# 4_ADC.net
KiCad netlist of a schematic drawn in Altium Designer
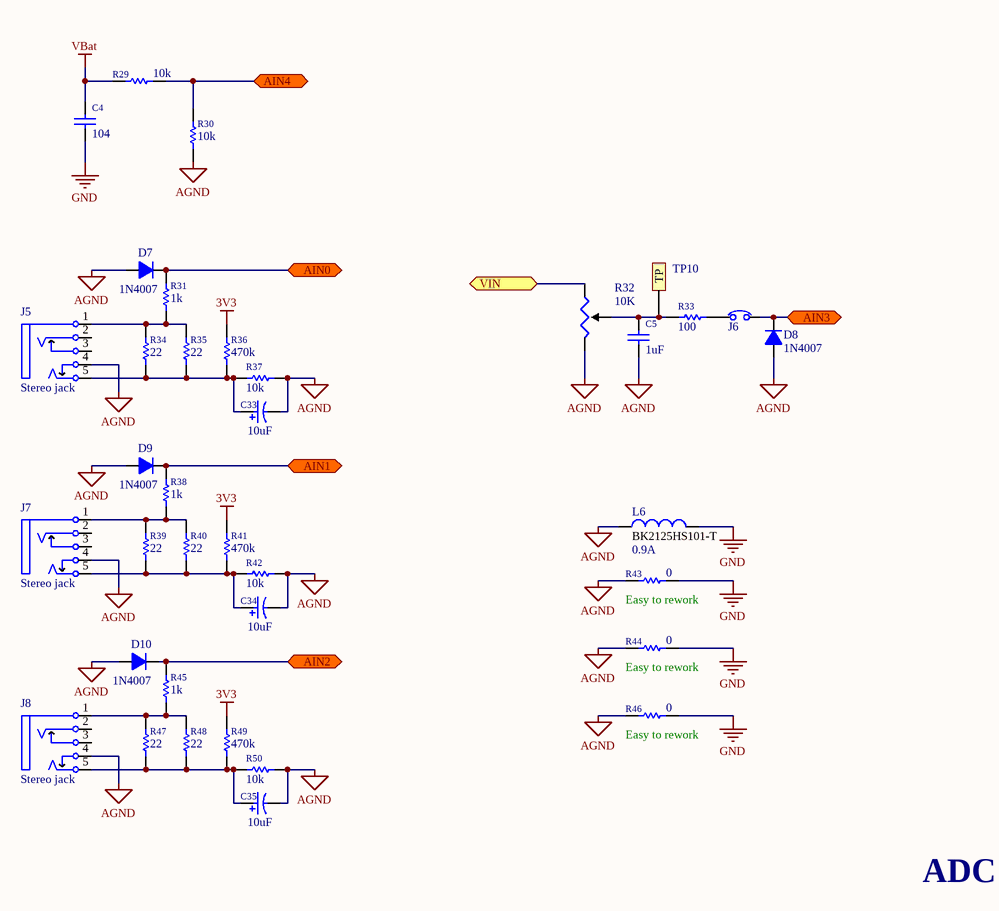
[diagram p0: 4. ADC.SchDoc]

(export (version "E")
  (design (tool "Eeschema 10.0.6"))
  (components
    (comp (ref "C4")
      (value "104")
      (footprint "sm-0603-c")
      (description "CAP CER 10000PF 16V 0603")
      (fields (field (name "MANUFACTURER") "Taiyo Yuden") (field (name "PART") "EMK107SD103JA-T"))
      (libsource (lib "My_Integrated_Library") (part "Capacitor"))
    )
    (comp (ref "C5")
      (value "1uF")
      (footprint "sm-0603-c")
      (description "CAP CER 10000PF 16V 0603")
      (fields (field (name "MANUFACTURER") "Taiyo Yuden") (field (name "PART") "EMK107SD103JA-T"))
      (libsource (lib "My_Integrated_Library") (part "Capacitor"))
    )
    (comp (ref "C33")
      (value "10uF")
      (footprint "Cap SMD Tant 10u")
      (description "CAP CER 10UF 6.3V X5R 1206")
      (fields (field (name "MANUFACTURER") "Samsung Electro-Mechanics") (field (name "VOLTAGE") "6.3V"))
      (libsource (lib "My_Integrated_Library") (part "Cap_Pol"))
    )
    (comp (ref "C34")
      (value "10uF")
      (footprint "Cap SMD Tant 10u")
      (description "CAP CER 10UF 6.3V X5R 1206")
      (fields (field (name "MANUFACTURER") "Samsung Electro-Mechanics") (field (name "VOLTAGE") "6.3V"))
      (libsource (lib "My_Integrated_Library") (part "Cap_Pol"))
    )
    (comp (ref "C35")
      (value "10uF")
      (footprint "Cap SMD Tant 10u")
      (description "CAP CER 10UF 6.3V X5R 1206")
      (fields (field (name "MANUFACTURER") "Samsung Electro-Mechanics") (field (name "VOLTAGE") "6.3V"))
      (libsource (lib "My_Integrated_Library") (part "Cap_Pol"))
    )
    (comp (ref "D7")
      (value "1N4007")
      (footprint "SOD-123")
      (description "DIODE 100V/1A")
      (fields (field (name "PART") "Diode 1N4007") (field (name "MANUFACTURER") "TOSHIBA"))
      (libsource (lib "My_Integrated_Library") (part "Diode 1N4007"))
    )
    (comp (ref "D8")
      (value "1N4007")
      (footprint "SOD-123")
      (description "DIODE 100V/1A")
      (fields (field (name "PART") "Diode 1N4007") (field (name "MANUFACTURER") "TOSHIBA"))
      (libsource (lib "My_Integrated_Library") (part "Diode 1N4007"))
    )
    (comp (ref "D9")
      (value "1N4007")
      (footprint "SOD-123")
      (description "DIODE 100V/1A")
      (fields (field (name "PART") "Diode 1N4007") (field (name "MANUFACTURER") "TOSHIBA"))
      (libsource (lib "My_Integrated_Library") (part "Diode 1N4007"))
    )
    (comp (ref "D10")
      (value "1N4007")
      (footprint "SOD-123")
      (description "DIODE 100V/1A")
      (fields (field (name "PART") "Diode 1N4007") (field (name "MANUFACTURER") "TOSHIBA"))
      (libsource (lib "My_Integrated_Library") (part "Diode 1N4007"))
    )
    (comp (ref "J5")
      (value "Stereo jack")
      (footprint "Audio Stereo Jack")
      (description "Stereo audio jack")
      (libsource (lib "SangNgocLe") (part "Audio Jack"))
    )
    (comp (ref "J6")
      (value "jumper selector")
      (footprint "CON.HDR1X2")
      (libsource (lib "My_Integrated_Library") (part "jumper selector"))
    )
    (comp (ref "J7")
      (value "Stereo jack")
      (footprint "Audio Stereo Jack")
      (description "Stereo audio jack")
      (libsource (lib "SangNgocLe") (part "Audio Jack"))
    )
    (comp (ref "J8")
      (value "Stereo jack")
      (footprint "Audio Stereo Jack")
      (description "Stereo audio jack")
      (libsource (lib "SangNgocLe") (part "Audio Jack"))
    )
    (comp (ref "L6")
      (value "BK2125HS101-T")
      (footprint "L2012-0805")
      (description "FERRITE BEAD 100 OHM 0805 1LN")
      (fields (field (name "MANUFACTURER") "Taiyo Yuden") (field (name "CURRENT") "0.9A"))
      (libsource (lib "My_Integrated_Library") (part "Inductor"))
    )
    (comp (ref "R29")
      (value "10k")
      (footprint "SM-0603-R")
      (description "RES SMD 10K OHM 5% 1/10W 0603")
      (fields (field (name "MANUFACTURER") "Panasonic Electronic Components") (field (name "POWER") "1/10W"))
      (libsource (lib "My_Integrated_Library") (part "Resistor"))
    )
    (comp (ref "R30")
      (value "10k")
      (footprint "SM-0603-R")
      (description "RES SMD 10K OHM 5% 1/10W 0603")
      (fields (field (name "MANUFACTURER") "Panasonic Electronic Components") (field (name "POWER") "1/10W"))
      (libsource (lib "My_Integrated_Library") (part "Resistor"))
    )
    (comp (ref "R31")
      (value "1k")
      (footprint "SM-0603-R")
      (description "RES SMD 10K OHM 5% 1/10W 0603")
      (fields (field (name "MANUFACTURER") "Panasonic Electronic Components") (field (name "PART") "10k"))
      (libsource (lib "My_Integrated_Library") (part "Resistor"))
    )
    (comp (ref "R32")
      (value "10K")
      (footprint "TRIM Rect")
      (description "Res var, Rectangle Trimmer")
      (fields (field (name "PART") "Trimmer"))
      (libsource (lib "My_Integrated_Library") (part "Trimmer"))
    )
    (comp (ref "R33")
      (value "100")
      (footprint "SM-0603-R")
      (description "RES SMD 10K OHM 5% 1/10W 0603")
      (fields (field (name "MANUFACTURER") "Panasonic Electronic Components") (field (name "PART") "10k"))
      (libsource (lib "My_Integrated_Library") (part "Resistor"))
    )
    (comp (ref "R34")
      (value "22")
      (footprint "SM-RES-1206")
      (description "RES SMD 10K OHM 5% 1/10W 0603")
      (fields (field (name "MANUFACTURER") "Panasonic Electronic Components") (field (name "PART") "10k"))
      (libsource (lib "My_Integrated_Library") (part "Resistor"))
    )
    (comp (ref "R35")
      (value "22")
      (footprint "SM-0603-R")
      (description "RES SMD 10K OHM 5% 1/10W 0603")
      (fields (field (name "MANUFACTURER") "Panasonic Electronic Components") (field (name "PART") "10k"))
      (libsource (lib "My_Integrated_Library") (part "Resistor"))
    )
    (comp (ref "R36")
      (value "470k")
      (footprint "SM-0603-R")
      (description "RES SMD 10K OHM 5% 1/10W 0603")
      (fields (field (name "MANUFACTURER") "Panasonic Electronic Components") (field (name "PART") "10k"))
      (libsource (lib "My_Integrated_Library") (part "Resistor"))
    )
    (comp (ref "R37")
      (value "10k")
      (footprint "SM-0603-R")
      (description "RES SMD 10K OHM 5% 1/10W 0603")
      (fields (field (name "MANUFACTURER") "Panasonic Electronic Components") (field (name "POWER") "1/10W"))
      (libsource (lib "My_Integrated_Library") (part "Resistor"))
    )
    (comp (ref "R38")
      (value "1k")
      (footprint "SM-0603-R")
      (description "RES SMD 10K OHM 5% 1/10W 0603")
      (fields (field (name "MANUFACTURER") "Panasonic Electronic Components") (field (name "PART") "10k"))
      (libsource (lib "My_Integrated_Library") (part "Resistor"))
    )
    (comp (ref "R39")
      (value "22")
      (footprint "SM-RES-1206")
      (description "RES SMD 10K OHM 5% 1/10W 0603")
      (fields (field (name "MANUFACTURER") "Panasonic Electronic Components") (field (name "PART") "10k"))
      (libsource (lib "My_Integrated_Library") (part "Resistor"))
    )
    (comp (ref "R40")
      (value "22")
      (footprint "SM-0603-R")
      (description "RES SMD 10K OHM 5% 1/10W 0603")
      (fields (field (name "MANUFACTURER") "Panasonic Electronic Components") (field (name "PART") "10k"))
      (libsource (lib "My_Integrated_Library") (part "Resistor"))
    )
    (comp (ref "R41")
      (value "470k")
      (footprint "SM-0603-R")
      (description "RES SMD 10K OHM 5% 1/10W 0603")
      (fields (field (name "MANUFACTURER") "Panasonic Electronic Components") (field (name "PART") "10k"))
      (libsource (lib "My_Integrated_Library") (part "Resistor"))
    )
    (comp (ref "R42")
      (value "10k")
      (footprint "SM-0603-R")
      (description "RES SMD 10K OHM 5% 1/10W 0603")
      (fields (field (name "MANUFACTURER") "Panasonic Electronic Components") (field (name "POWER") "1/10W"))
      (libsource (lib "My_Integrated_Library") (part "Resistor"))
    )
    (comp (ref "R43")
      (value "0")
      (footprint "R2012-0805")
      (description "RES SMD 0 OHM JUMPER 1/10W 0805")
      (fields (field (name "MANUFACTURER") "Panasonic Electronic Components") (field (name "POWER") "1/10W"))
      (libsource (lib "My_Integrated_Library") (part "Resistor"))
    )
    (comp (ref "R44")
      (value "0")
      (footprint "R2012-0805")
      (description "RES SMD 0 OHM JUMPER 1/10W 0805")
      (fields (field (name "MANUFACTURER") "Panasonic Electronic Components") (field (name "POWER") "1/10W"))
      (libsource (lib "My_Integrated_Library") (part "Resistor"))
    )
    (comp (ref "R45")
      (value "1k")
      (footprint "SM-0603-R")
      (description "RES SMD 10K OHM 5% 1/10W 0603")
      (fields (field (name "MANUFACTURER") "Panasonic Electronic Components") (field (name "PART") "10k"))
      (libsource (lib "My_Integrated_Library") (part "Resistor"))
    )
    (comp (ref "R46")
      (value "0")
      (footprint "R2012-0805")
      (description "RES SMD 0 OHM JUMPER 1/10W 0805")
      (fields (field (name "MANUFACTURER") "Panasonic Electronic Components") (field (name "POWER") "1/10W"))
      (libsource (lib "My_Integrated_Library") (part "Resistor"))
    )
    (comp (ref "R47")
      (value "22")
      (footprint "SM-RES-1206")
      (description "RES SMD 10K OHM 5% 1/10W 0603")
      (fields (field (name "MANUFACTURER") "Panasonic Electronic Components") (field (name "PART") "10k"))
      (libsource (lib "My_Integrated_Library") (part "Resistor"))
    )
    (comp (ref "R48")
      (value "22")
      (footprint "SM-0603-R")
      (description "RES SMD 10K OHM 5% 1/10W 0603")
      (fields (field (name "MANUFACTURER") "Panasonic Electronic Components") (field (name "PART") "10k"))
      (libsource (lib "My_Integrated_Library") (part "Resistor"))
    )
    (comp (ref "R49")
      (value "470k")
      (footprint "SM-0603-R")
      (description "RES SMD 10K OHM 5% 1/10W 0603")
      (fields (field (name "MANUFACTURER") "Panasonic Electronic Components") (field (name "PART") "10k"))
      (libsource (lib "My_Integrated_Library") (part "Resistor"))
    )
    (comp (ref "R50")
      (value "10k")
      (footprint "SM-0603-R")
      (description "RES SMD 10K OHM 5% 1/10W 0603")
      (fields (field (name "MANUFACTURER") "Panasonic Electronic Components") (field (name "POWER") "1/10W"))
      (libsource (lib "My_Integrated_Library") (part "Resistor"))
    )
    (comp (ref "TP10")
      (value "4V3_PG")
      (footprint "TP")
      (description "Test Point")
      (libsource (lib "My_Integrated_Library") (part "Test Point"))
    )
  )
  (nets
    (net (code "1") (name "/AIN0") (class "Default")
      (node (ref "D7") (pin "2") (pinfunction "K_2") (pintype "passive"))
      (node (ref "R31") (pin "2") (pinfunction "2_2") (pintype "passive"))
    )
    (net (code "2") (name "/AIN1") (class "Default")
      (node (ref "D9") (pin "2") (pinfunction "K_2") (pintype "passive"))
      (node (ref "R38") (pin "2") (pinfunction "2_2") (pintype "passive"))
    )
    (net (code "3") (name "/AIN2") (class "Default")
      (node (ref "D10") (pin "2") (pinfunction "K_2") (pintype "passive"))
      (node (ref "R45") (pin "2") (pinfunction "2_2") (pintype "passive"))
    )
    (net (code "4") (name "/AIN3") (class "Default")
      (node (ref "D8") (pin "2") (pinfunction "K_2") (pintype "passive"))
      (node (ref "J6") (pin "2") (pinfunction "2_2") (pintype "passive"))
    )
    (net (code "5") (name "/AIN4") (class "Default")
      (node (ref "R29") (pin "2") (pinfunction "2_2") (pintype "passive"))
      (node (ref "R30") (pin "2") (pinfunction "2_2") (pintype "passive"))
    )
    (net (code "6") (name "/VIN") (class "Default")
      (node (ref "R32") (pin "1") (pinfunction "1_1") (pintype "passive"))
    )
    (net (code "7") (name "3V3") (class "Default")
      (node (ref "R36") (pin "2") (pinfunction "2_2") (pintype "passive"))
      (node (ref "R41") (pin "2") (pinfunction "2_2") (pintype "passive"))
      (node (ref "R49") (pin "2") (pinfunction "2_2") (pintype "passive"))
    )
    (net (code "8") (name "AGND") (class "Default")
      (node (ref "C33") (pin "2") (pinfunction "2_2") (pintype "passive"))
      (node (ref "C34") (pin "2") (pinfunction "2_2") (pintype "passive"))
      (node (ref "C35") (pin "2") (pinfunction "2_2") (pintype "passive"))
      (node (ref "C5") (pin "2") (pinfunction "2_2") (pintype "passive"))
      (node (ref "D10") (pin "1") (pinfunction "A_1") (pintype "passive"))
      (node (ref "D7") (pin "1") (pinfunction "A_1") (pintype "passive"))
      (node (ref "D8") (pin "1") (pinfunction "A_1") (pintype "passive"))
      (node (ref "D9") (pin "1") (pinfunction "A_1") (pintype "passive"))
      (node (ref "J5") (pin "4") (pinfunction "R2_4") (pintype "power_in"))
      (node (ref "J7") (pin "4") (pinfunction "R2_4") (pintype "power_in"))
      (node (ref "J8") (pin "4") (pinfunction "R2_4") (pintype "power_in"))
      (node (ref "L6") (pin "1") (pinfunction "1_1") (pintype "passive"))
      (node (ref "R30") (pin "1") (pinfunction "1_1") (pintype "passive"))
      (node (ref "R32") (pin "3") (pinfunction "3_3") (pintype "passive"))
      (node (ref "R37") (pin "1") (pinfunction "1_1") (pintype "passive"))
      (node (ref "R42") (pin "1") (pinfunction "1_1") (pintype "passive"))
      (node (ref "R43") (pin "1") (pinfunction "1_1") (pintype "passive"))
      (node (ref "R44") (pin "1") (pinfunction "1_1") (pintype "passive"))
      (node (ref "R46") (pin "1") (pinfunction "1_1") (pintype "passive"))
      (node (ref "R50") (pin "1") (pinfunction "1_1") (pintype "passive"))
    )
    (net (code "9") (name "GND") (class "Default")
      (node (ref "C4") (pin "2") (pinfunction "2_2") (pintype "passive"))
      (node (ref "L6") (pin "2") (pinfunction "2_2") (pintype "passive"))
      (node (ref "R43") (pin "2") (pinfunction "2_2") (pintype "passive"))
      (node (ref "R44") (pin "2") (pinfunction "2_2") (pintype "passive"))
      (node (ref "R46") (pin "2") (pinfunction "2_2") (pintype "passive"))
    )
    (net (code "10") (name "Net-(J5-GND)") (class "Default")
      (node (ref "J5") (pin "1") (pinfunction "GND_1") (pintype "passive"))
      (node (ref "R31") (pin "1") (pinfunction "1_1") (pintype "passive"))
      (node (ref "R34") (pin "2") (pinfunction "2_2") (pintype "passive"))
      (node (ref "R35") (pin "2") (pinfunction "2_2") (pintype "passive"))
    )
    (net (code "11") (name "Net-(J5-S2)") (class "Default")
      (node (ref "C33") (pin "1") (pinfunction "1_1") (pintype "passive"))
      (node (ref "J5") (pin "5") (pinfunction "S2_5") (pintype "power_in"))
      (node (ref "R34") (pin "1") (pinfunction "1_1") (pintype "passive"))
      (node (ref "R35") (pin "1") (pinfunction "1_1") (pintype "passive"))
      (node (ref "R36") (pin "1") (pinfunction "1_1") (pintype "passive"))
      (node (ref "R37") (pin "2") (pinfunction "2_2") (pintype "passive"))
    )
    (net (code "12") (name "Net-(J6-Pad1)") (class "Default")
      (node (ref "J6") (pin "1") (pinfunction "1_1") (pintype "passive"))
      (node (ref "R33") (pin "1") (pinfunction "1_1") (pintype "passive"))
    )
    (net (code "13") (name "Net-(J7-GND)") (class "Default")
      (node (ref "J7") (pin "1") (pinfunction "GND_1") (pintype "passive"))
      (node (ref "R38") (pin "1") (pinfunction "1_1") (pintype "passive"))
      (node (ref "R39") (pin "2") (pinfunction "2_2") (pintype "passive"))
      (node (ref "R40") (pin "2") (pinfunction "2_2") (pintype "passive"))
    )
    (net (code "14") (name "Net-(J7-S2)") (class "Default")
      (node (ref "C34") (pin "1") (pinfunction "1_1") (pintype "passive"))
      (node (ref "J7") (pin "5") (pinfunction "S2_5") (pintype "power_in"))
      (node (ref "R39") (pin "1") (pinfunction "1_1") (pintype "passive"))
      (node (ref "R40") (pin "1") (pinfunction "1_1") (pintype "passive"))
      (node (ref "R41") (pin "1") (pinfunction "1_1") (pintype "passive"))
      (node (ref "R42") (pin "2") (pinfunction "2_2") (pintype "passive"))
    )
    (net (code "15") (name "Net-(J8-GND)") (class "Default")
      (node (ref "J8") (pin "1") (pinfunction "GND_1") (pintype "passive"))
      (node (ref "R45") (pin "1") (pinfunction "1_1") (pintype "passive"))
      (node (ref "R47") (pin "2") (pinfunction "2_2") (pintype "passive"))
      (node (ref "R48") (pin "2") (pinfunction "2_2") (pintype "passive"))
    )
    (net (code "16") (name "Net-(J8-S2)") (class "Default")
      (node (ref "C35") (pin "1") (pinfunction "1_1") (pintype "passive"))
      (node (ref "J8") (pin "5") (pinfunction "S2_5") (pintype "power_in"))
      (node (ref "R47") (pin "1") (pinfunction "1_1") (pintype "passive"))
      (node (ref "R48") (pin "1") (pinfunction "1_1") (pintype "passive"))
      (node (ref "R49") (pin "1") (pinfunction "1_1") (pintype "passive"))
      (node (ref "R50") (pin "2") (pinfunction "2_2") (pintype "passive"))
    )
    (net (code "17") (name "Net-(TP10-TP)") (class "Default")
      (node (ref "C5") (pin "1") (pinfunction "1_1") (pintype "passive"))
      (node (ref "R32") (pin "2") (pinfunction "2_2") (pintype "passive"))
      (node (ref "R33") (pin "2") (pinfunction "2_2") (pintype "passive"))
      (node (ref "TP10") (pin "1") (pinfunction "TP_1") (pintype "passive"))
    )
    (net (code "18") (name "VBat") (class "Default")
      (node (ref "C4") (pin "1") (pinfunction "1_1") (pintype "passive"))
      (node (ref "R29") (pin "1") (pinfunction "1_1") (pintype "passive"))
    )
    (net (code "19") (name "unconnected-(J5-R1-Pad3)") (class "Default")
      (node (ref "J5") (pin "3") (pinfunction "R1_3") (pintype "power_in"))
    )
    (net (code "20") (name "unconnected-(J5-S1-Pad2)") (class "Default")
      (node (ref "J5") (pin "2") (pinfunction "S1_2") (pintype "power_in"))
    )
    (net (code "21") (name "unconnected-(J7-R1-Pad3)") (class "Default")
      (node (ref "J7") (pin "3") (pinfunction "R1_3") (pintype "power_in"))
    )
    (net (code "22") (name "unconnected-(J7-S1-Pad2)") (class "Default")
      (node (ref "J7") (pin "2") (pinfunction "S1_2") (pintype "power_in"))
    )
    (net (code "23") (name "unconnected-(J8-R1-Pad3)") (class "Default")
      (node (ref "J8") (pin "3") (pinfunction "R1_3") (pintype "power_in"))
    )
    (net (code "24") (name "unconnected-(J8-S1-Pad2)") (class "Default")
      (node (ref "J8") (pin "2") (pinfunction "S1_2") (pintype "power_in"))
    )
  )
)
